# FuelGauge_Sheet.net
KiCad netlist of a schematic drawn in Altium Designer
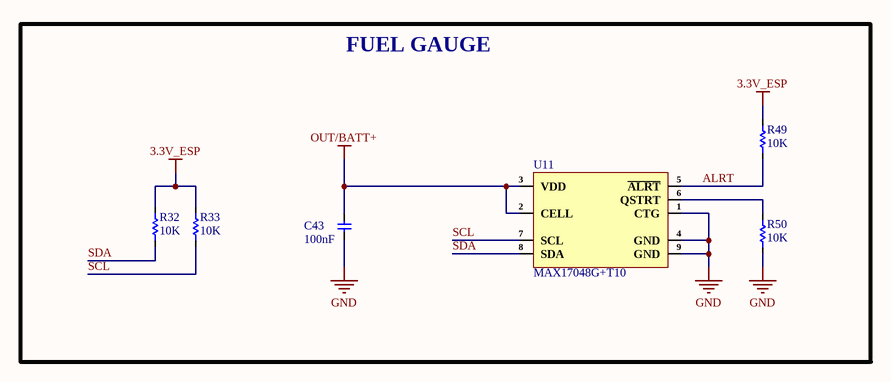
[diagram p0: FuelGauge_Sheet.SchDoc]

(export (version "E")
  (design (tool "Eeschema 10.0.6"))
  (components
    (comp (ref "C43")
      (value "100nF")
      (footprint "cap-0402")
      (description "CAP CER 0.1UF 50V X7R 0402")
      (fields
        (field (name "MANUFACTURER") "TDK")
        (field (name "MANUFACTURER PART NUMBER") "C1005X7R1H104KT000F")
      )
      (libsource (lib "eSpark Libraries") (part "C1005X7R1H104KT000F"))
    )
    (comp (ref "R32")
      (value "10K")
      (footprint "Res-0402")
      (description "RES 10K OHM 1% 1/16W 0402")
      (fields
        (field (name "MANUFACTURER") "Yageo")
        (field (name "MANUFACTURER PART NUMBER") "RC0402FR-0710KL")
      )
      (libsource (lib "eSpark Libraries") (part "RC0402FR-0710KL"))
    )
    (comp (ref "R33")
      (value "10K")
      (footprint "Res-0402")
      (description "RES 10K OHM 1% 1/16W 0402")
      (fields
        (field (name "MANUFACTURER") "Yageo")
        (field (name "MANUFACTURER PART NUMBER") "RC0402FR-0710KL")
      )
      (libsource (lib "eSpark Libraries") (part "RC0402FR-0710KL"))
    )
    (comp (ref "R49")
      (value "10K")
      (footprint "Res-0402")
      (description "RES 10K OHM 1% 1/16W 0402")
      (fields
        (field (name "MANUFACTURER") "Yageo")
        (field (name "MANUFACTURER PART NUMBER") "RC0402FR-0710KL")
      )
      (libsource (lib "eSpark Libraries") (part "RC0402FR-0710KL"))
    )
    (comp (ref "R50")
      (value "10K")
      (footprint "Res-0402")
      (description "RES 10K OHM 1% 1/16W 0402")
      (fields
        (field (name "MANUFACTURER") "Yageo")
        (field (name "MANUFACTURER PART NUMBER") "RC0402FR-0710KL")
      )
      (libsource (lib "eSpark Libraries") (part "RC0402FR-0710KL"))
    )
    (comp (ref "U11")
      (value "MAX17048G+T10")
      (footprint "8-TDFN-EP (2x2)")
      (description "IC BATT MON LI-ION 1CELL 8TDFN")
      (fields (field (name "MANUFACTURER") "Maxim") (field (name "LCSC PART NUMBER") "C2682616"))
      (libsource (lib "eSpark Libraries") (part "MAX17048G+T10"))
    )
  )
  (nets
    (net (code "1") (name "/ALRT") (class "Default")
      (node (ref "R49") (pin "1") (pinfunction "1_1") (pintype "passive"))
      (node (ref "U11") (pin "5") (pinfunction "~{ALRT}_5") (pintype "passive"))
    )
    (net (code "2") (name "/SCL") (class "Default")
      (node (ref "R33") (pin "1") (pinfunction "1_1") (pintype "passive"))
      (node (ref "U11") (pin "7") (pinfunction "SCL_7") (pintype "passive"))
    )
    (net (code "3") (name "/SDA") (class "Default")
      (node (ref "R32") (pin "1") (pinfunction "1_1") (pintype "passive"))
      (node (ref "U11") (pin "8") (pinfunction "SDA_8") (pintype "passive"))
    )
    (net (code "4") (name "3.3V_ESP") (class "Default")
      (node (ref "R32") (pin "2") (pinfunction "2_2") (pintype "passive"))
      (node (ref "R33") (pin "2") (pinfunction "2_2") (pintype "passive"))
      (node (ref "R49") (pin "2") (pinfunction "2_2") (pintype "passive"))
    )
    (net (code "5") (name "GND") (class "Default")
      (node (ref "C43") (pin "2") (pinfunction "2_2") (pintype "passive"))
      (node (ref "R50") (pin "1") (pinfunction "1_1") (pintype "passive"))
      (node (ref "U11") (pin "1") (pinfunction "CTG_1") (pintype "passive"))
      (node (ref "U11") (pin "4") (pinfunction "GND_4") (pintype "passive"))
      (node (ref "U11") (pin "9") (pinfunction "GND_9") (pintype "passive"))
    )
    (net (code "6") (name "Net-(U11-QSTRT)") (class "Default")
      (node (ref "R50") (pin "2") (pinfunction "2_2") (pintype "passive"))
      (node (ref "U11") (pin "6") (pinfunction "QSTRT_6") (pintype "passive"))
    )
    (net (code "7") (name "OUT{slash}BATT+") (class "Default")
      (node (ref "C43") (pin "1") (pinfunction "1_1") (pintype "passive"))
      (node (ref "U11") (pin "2") (pinfunction "CELL_2") (pintype "passive"))
      (node (ref "U11") (pin "3") (pinfunction "VDD_3") (pintype "passive"))
    )
  )
)
